# team_throttle_control_draft_2.net
KiCad netlist of a schematic drawn in EAGLE
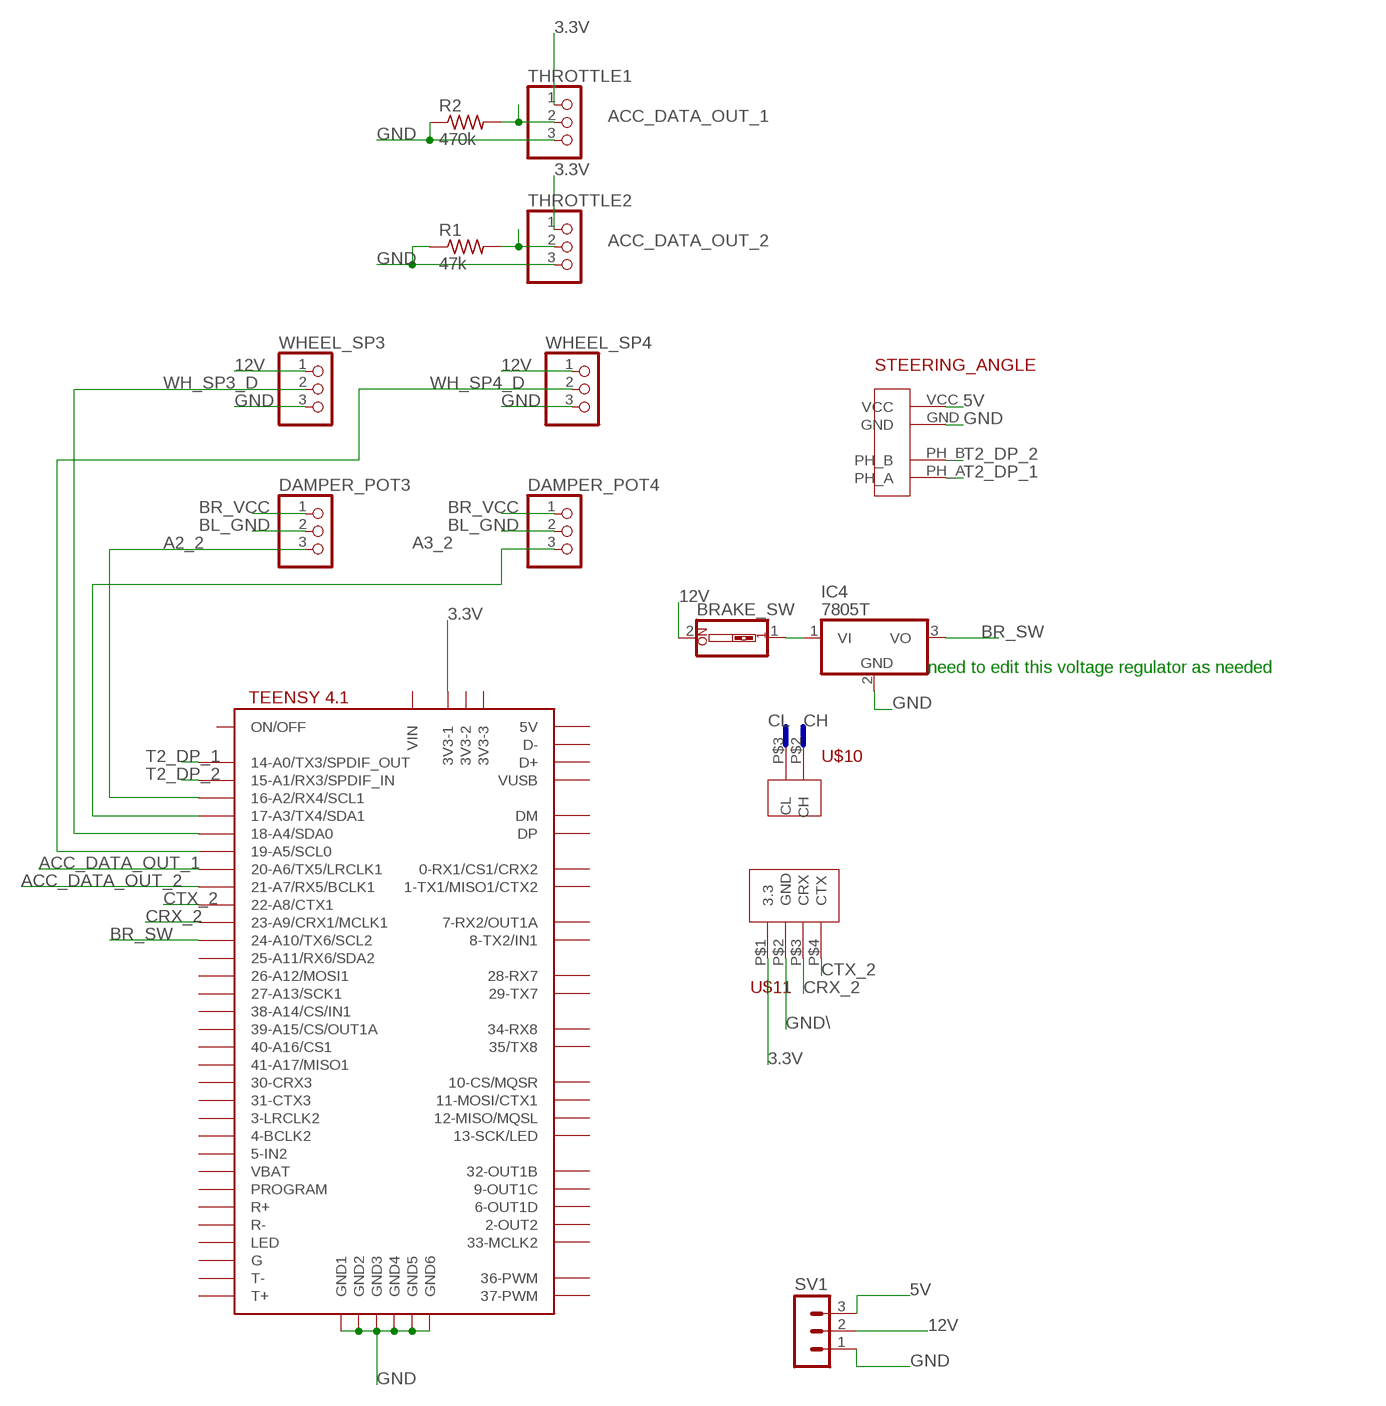
[diagram p0: schematic, sheet 1]

(export (version "E")
  (design (tool "Eeschema 10.0.6"))
  (components
    (comp (ref "BRAKE_SW")
      (value "SW_DIP-1")
      (footprint "eagle-import:EDG-01")
      (libsource (lib "eagle-import") (part "SW_DIP-1"))
    )
    (comp (ref "DAMPER_POT3")
      (value "PINHD-1X3CB")
      (footprint "eagle-import:1X03-CLEANBIG")
      (libsource (lib "eagle-import") (part "PINHD-1X3CB"))
    )
    (comp (ref "DAMPER_POT4")
      (value "PINHD-1X3CB")
      (footprint "eagle-import:1X03-CLEANBIG")
      (libsource (lib "eagle-import") (part "PINHD-1X3CB"))
    )
    (comp (ref "IC4")
      (value "7805T")
      (footprint "eagle-import:TO220H")
      (libsource (lib "eagle-import") (part "78T05"))
    )
    (comp (ref "R1")
      (value "47k")
      (footprint "eagle-import:0204_7")
      (libsource (lib "eagle-import") (part "R-US_0204/7"))
    )
    (comp (ref "R2")
      (value "470k")
      (footprint "eagle-import:0204_7")
      (libsource (lib "eagle-import") (part "R-US_0204/7"))
    )
    (comp (ref "STEERING_ANGLE")
      (value "ROTARY_ENCODER")
      (footprint "eagle-import:ROTARY_ENCODER")
      (libsource (lib "eagle-import") (part "ROTARY_ENCODER"))
    )
    (comp (ref "SV1")
      (value "MA03-1")
      (footprint "eagle-import:MA03-1")
      (libsource (lib "eagle-import") (part "MA03-1"))
    )
    (comp (ref "THROTTLE1")
      (value "PINHD-1X3")
      (footprint "eagle-import:1X03")
      (libsource (lib "eagle-import") (part "PINHD-1X3"))
    )
    (comp (ref "THROTTLE2")
      (value "PINHD-1X3")
      (footprint "eagle-import:1X03")
      (libsource (lib "eagle-import") (part "PINHD-1X3"))
    )
    (comp (ref "U$3")
      (value "TEENSY41")
      (footprint "eagle-import:TEENSY41")
      (libsource (lib "eagle-import") (part "TEENSY41"))
    )
    (comp (ref "U$10")
      (value "CAN_BUS")
      (footprint "eagle-import:CAN_BUS")
      (libsource (lib "eagle-import") (part "CAN_BUS"))
    )
    (comp (ref "U$11")
      (value "CAN_TEE")
      (footprint "eagle-import:CAN_TEN")
      (libsource (lib "eagle-import") (part "CAN_TEE"))
    )
    (comp (ref "WHEEL_SP3")
      (value "PINHD-1X3")
      (footprint "eagle-import:1X03")
      (libsource (lib "eagle-import") (part "PINHD-1X3"))
    )
    (comp (ref "WHEEL_SP4")
      (value "PINHD-1X3")
      (footprint "eagle-import:1X03")
      (libsource (lib "eagle-import") (part "PINHD-1X3"))
    )
  )
  (nets
    (net (code "3") (name "/3.3V") (class "Default")
      (node (ref "THROTTLE1") (pin "1") (pinfunction "1_1") (pintype "passive"))
      (node (ref "THROTTLE2") (pin "1") (pinfunction "1_1") (pintype "passive"))
      (node (ref "U$11") (pin "P$1") (pinfunction "3.3_P$1") (pintype "bidirectional"))
      (node (ref "U$3") (pin "3V3-1") (pinfunction "3V3-1_3V3-1") (pintype "bidirectional"))
    )
    (net (code "4") (name "/5V") (class "Default")
      (node (ref "STEERING_ANGLE") (pin "VCC") (pinfunction "VCC_VCC") (pintype "bidirectional"))
      (node (ref "SV1") (pin "3") (pinfunction "3_3") (pintype "passive"))
    )
    (net (code "5") (name "/12V") (class "Default")
      (node (ref "BRAKE_SW") (pin "2") (pinfunction "2_2") (pintype "passive"))
      (node (ref "SV1") (pin "2") (pinfunction "2_2") (pintype "passive"))
      (node (ref "WHEEL_SP3") (pin "1") (pinfunction "1_1") (pintype "passive"))
      (node (ref "WHEEL_SP4") (pin "1") (pinfunction "1_1") (pintype "passive"))
    )
    (net (code "6") (name "/A2_2") (class "Default")
      (node (ref "DAMPER_POT3") (pin "3") (pinfunction "3_3") (pintype "passive"))
      (node (ref "U$3") (pin "16-A2/RX4/SCL1") (pinfunction "16-A2/RX4/SCL1_16-A2/RX4/SCL1") (pintype "bidirectional"))
    )
    (net (code "7") (name "/A3_2") (class "Default")
      (node (ref "DAMPER_POT4") (pin "3") (pinfunction "3_3") (pintype "passive"))
      (node (ref "U$3") (pin "17-A3/TX4/SDA1") (pinfunction "17-A3/TX4/SDA1_17-A3/TX4/SDA1") (pintype "bidirectional"))
    )
    (net (code "8") (name "/ACC_DATA_OUT_1") (class "Default")
      (node (ref "R2") (pin "2") (pinfunction "2_2") (pintype "passive"))
      (node (ref "THROTTLE1") (pin "2") (pinfunction "2_2") (pintype "passive"))
      (node (ref "U$3") (pin "20-A6/TX5/LRCLK1") (pinfunction "20-A6/TX5/LRCLK1_20-A6/TX5/LRCLK1") (pintype "bidirectional"))
    )
    (net (code "9") (name "/ACC_DATA_OUT_2") (class "Default")
      (node (ref "R1") (pin "2") (pinfunction "2_2") (pintype "passive"))
      (node (ref "THROTTLE2") (pin "2") (pinfunction "2_2") (pintype "passive"))
      (node (ref "U$3") (pin "21-A7/RX5/BCLK1") (pinfunction "21-A7/RX5/BCLK1_21-A7/RX5/BCLK1") (pintype "bidirectional"))
    )
    (net (code "10") (name "/BL_GND") (class "Default")
      (node (ref "DAMPER_POT3") (pin "2") (pinfunction "2_2") (pintype "passive"))
      (node (ref "DAMPER_POT4") (pin "2") (pinfunction "2_2") (pintype "passive"))
    )
    (net (code "11") (name "/BR_SW") (class "Default")
      (node (ref "IC4") (pin "3") (pinfunction "VO_3") (pintype "passive"))
      (node (ref "U$3") (pin "24-A10/TX6/SCL2") (pinfunction "24-A10/TX6/SCL2_24-A10/TX6/SCL2") (pintype "bidirectional"))
    )
    (net (code "12") (name "/BR_VCC") (class "Default")
      (node (ref "DAMPER_POT3") (pin "1") (pinfunction "1_1") (pintype "passive"))
      (node (ref "DAMPER_POT4") (pin "1") (pinfunction "1_1") (pintype "passive"))
    )
    (net (code "13") (name "/CRX_2") (class "Default")
      (node (ref "U$11") (pin "P$3") (pinfunction "CRX_P$3") (pintype "bidirectional"))
      (node (ref "U$3") (pin "23-A9/CRX1/MCLK1") (pinfunction "23-A9/CRX1/MCLK1_23-A9/CRX1/MCLK1") (pintype "bidirectional"))
    )
    (net (code "14") (name "/CTX_2") (class "Default")
      (node (ref "U$11") (pin "P$4") (pinfunction "CTX_P$4") (pintype "bidirectional"))
      (node (ref "U$3") (pin "22-A8/CTX1") (pinfunction "22-A8/CTX1_22-A8/CTX1") (pintype "bidirectional"))
    )
    (net (code "15") (name "/GND") (class "Default")
      (node (ref "IC4") (pin "2") (pinfunction "GND_2") (pintype "passive"))
      (node (ref "R1") (pin "1") (pinfunction "1_1") (pintype "passive"))
      (node (ref "R2") (pin "1") (pinfunction "1_1") (pintype "passive"))
      (node (ref "STEERING_ANGLE") (pin "GND") (pinfunction "GND_GND") (pintype "bidirectional"))
      (node (ref "SV1") (pin "1") (pinfunction "1_1") (pintype "passive"))
      (node (ref "THROTTLE1") (pin "3") (pinfunction "3_3") (pintype "passive"))
      (node (ref "THROTTLE2") (pin "3") (pinfunction "3_3") (pintype "passive"))
      (node (ref "U$3") (pin "GND1") (pinfunction "GND1_GND1") (pintype "bidirectional"))
      (node (ref "U$3") (pin "GND2") (pinfunction "GND2_GND2") (pintype "bidirectional"))
      (node (ref "U$3") (pin "GND3") (pinfunction "GND3_GND3") (pintype "bidirectional"))
      (node (ref "U$3") (pin "GND4") (pinfunction "GND4_GND4") (pintype "bidirectional"))
      (node (ref "U$3") (pin "GND5") (pinfunction "GND5_GND5") (pintype "bidirectional"))
      (node (ref "U$3") (pin "GND6") (pinfunction "GND6_GND6") (pintype "bidirectional"))
      (node (ref "WHEEL_SP3") (pin "3") (pinfunction "3_3") (pintype "passive"))
      (node (ref "WHEEL_SP4") (pin "3") (pinfunction "3_3") (pintype "passive"))
    )
    (net (code "16") (name "/GND\\") (class "Default")
      (node (ref "U$11") (pin "P$2") (pinfunction "GND_P$2") (pintype "bidirectional"))
    )
    (net (code "17") (name "/T2_DP_1") (class "Default")
      (node (ref "STEERING_ANGLE") (pin "PH_A") (pinfunction "PH_A_PH_A") (pintype "bidirectional"))
      (node (ref "U$3") (pin "14-A0/TX3/SPDIF_OUT") (pinfunction "14-A0/TX3/SPDIF_OUT_14-A0/TX3/SPDIF_OUT") (pintype "bidirectional"))
    )
    (net (code "18") (name "/T2_DP_2") (class "Default")
      (node (ref "STEERING_ANGLE") (pin "PH_B") (pinfunction "PH_B_PH_B") (pintype "bidirectional"))
      (node (ref "U$3") (pin "15-A1/RX3/SPDIF_IN") (pinfunction "15-A1/RX3/SPDIF_IN_15-A1/RX3/SPDIF_IN") (pintype "bidirectional"))
    )
    (net (code "19") (name "/WH_SP3_D") (class "Default")
      (node (ref "U$3") (pin "18-A4/SDA0") (pinfunction "18-A4/SDA0_18-A4/SDA0") (pintype "bidirectional"))
      (node (ref "WHEEL_SP3") (pin "2") (pinfunction "2_2") (pintype "passive"))
    )
    (net (code "20") (name "/WH_SP4_D") (class "Default")
      (node (ref "U$3") (pin "19-A5/SCL0") (pinfunction "19-A5/SCL0_19-A5/SCL0") (pintype "bidirectional"))
      (node (ref "WHEEL_SP4") (pin "2") (pinfunction "2_2") (pintype "passive"))
    )
    (net (code "21") (name "/{CH}") (class "Default")
      (node (ref "U$10") (pin "P$2") (pinfunction "CH_P$2") (pintype "bidirectional"))
    )
    (net (code "22") (name "/{CL}") (class "Default")
      (node (ref "U$10") (pin "P$3") (pinfunction "CL_P$3") (pintype "bidirectional"))
    )
    (net (code "23") (name "Net-(IC4-VI)") (class "Default")
      (node (ref "BRAKE_SW") (pin "1") (pinfunction "1_1") (pintype "passive"))
      (node (ref "IC4") (pin "1") (pinfunction "VI_1") (pintype "input"))
    )
    (net (code "24") (name "unconnected-(U$3-5V-Pad+5V)") (class "Default")
      (node (ref "U$3") (pin "+5V") (pinfunction "5V_+5V") (pintype "bidirectional"))
    )
    (net (code "25") (name "unconnected-(U$3-8-TX2{slash}IN1-Pad8-TX2{slash}IN2)") (class "Default")
      (node (ref "U$3") (pin "8-TX2/IN2") (pinfunction "8-TX2/IN1_8-TX2/IN2") (pintype "bidirectional"))
    )
    (net (code "26") (name "unconnected-(U$3-10-CS{slash}MQSR-Pad10-CS\\MQSR)") (class "Default")
      (node (ref "U$3") (pin "10-CS\\MQSR") (pinfunction "10-CS/MQSR_10-CS\\MQSR") (pintype "bidirectional"))
    )
    (net (code "27") (name "unconnected-(U$3-35{slash}TX8-Pad35-TX8)") (class "Default")
      (node (ref "U$3") (pin "35-TX8") (pinfunction "35/TX8_35-TX8") (pintype "bidirectional"))
    )
    (net (code "28") (name "unconnected-(U$3-Pad0-RX1{slash}CS1{slash}CRX2)") (class "Default")
      (node (ref "U$3") (pin "0-RX1/CS1/CRX2") (pinfunction "0-RX1/CS1/CRX2_0-RX1/CS1/CRX2") (pintype "bidirectional"))
    )
    (net (code "29") (name "unconnected-(U$3-Pad1-TX1{slash}MISO1{slash}CTX2)") (class "Default")
      (node (ref "U$3") (pin "1-TX1/MISO1/CTX2") (pinfunction "1-TX1/MISO1/CTX2_1-TX1/MISO1/CTX2") (pintype "bidirectional"))
    )
    (net (code "30") (name "unconnected-(U$3-Pad2-OUT2)") (class "Default")
      (node (ref "U$3") (pin "2-OUT2") (pinfunction "2-OUT2_2-OUT2") (pintype "bidirectional"))
    )
    (net (code "31") (name "unconnected-(U$3-Pad3-LRCLK2)") (class "Default")
      (node (ref "U$3") (pin "3-LRCLK2") (pinfunction "3-LRCLK2_3-LRCLK2") (pintype "bidirectional"))
    )
    (net (code "32") (name "unconnected-(U$3-Pad3V3-2)") (class "Default")
      (node (ref "U$3") (pin "3V3-2") (pinfunction "3V3-2_3V3-2") (pintype "bidirectional"))
    )
    (net (code "33") (name "unconnected-(U$3-Pad3V3-3)") (class "Default")
      (node (ref "U$3") (pin "3V3-3") (pinfunction "3V3-3_3V3-3") (pintype "bidirectional"))
    )
    (net (code "34") (name "unconnected-(U$3-Pad4-BCLK2)") (class "Default")
      (node (ref "U$3") (pin "4-BCLK2") (pinfunction "4-BCLK2_4-BCLK2") (pintype "bidirectional"))
    )
    (net (code "35") (name "unconnected-(U$3-Pad5-IN2)") (class "Default")
      (node (ref "U$3") (pin "5-IN2") (pinfunction "5-IN2_5-IN2") (pintype "bidirectional"))
    )
    (net (code "36") (name "unconnected-(U$3-Pad6-OUT1D)") (class "Default")
      (node (ref "U$3") (pin "6-OUT1D") (pinfunction "6-OUT1D_6-OUT1D") (pintype "bidirectional"))
    )
    (net (code "37") (name "unconnected-(U$3-Pad7-RX2{slash}OUT1A)") (class "Default")
      (node (ref "U$3") (pin "7-RX2/OUT1A") (pinfunction "7-RX2/OUT1A_7-RX2/OUT1A") (pintype "bidirectional"))
    )
    (net (code "38") (name "unconnected-(U$3-Pad9-OUT1C)") (class "Default")
      (node (ref "U$3") (pin "9-OUT1C") (pinfunction "9-OUT1C_9-OUT1C") (pintype "bidirectional"))
    )
    (net (code "39") (name "unconnected-(U$3-Pad11-MOSI{slash}CTX1)") (class "Default")
      (node (ref "U$3") (pin "11-MOSI/CTX1") (pinfunction "11-MOSI/CTX1_11-MOSI/CTX1") (pintype "bidirectional"))
    )
    (net (code "40") (name "unconnected-(U$3-Pad12-MISO{slash}MQSL)") (class "Default")
      (node (ref "U$3") (pin "12-MISO/MQSL") (pinfunction "12-MISO/MQSL_12-MISO/MQSL") (pintype "bidirectional"))
    )
    (net (code "41") (name "unconnected-(U$3-Pad13-SCK{slash}LED)") (class "Default")
      (node (ref "U$3") (pin "13-SCK/LED") (pinfunction "13-SCK/LED_13-SCK/LED") (pintype "bidirectional"))
    )
    (net (code "42") (name "unconnected-(U$3-Pad25-A11{slash}RX6{slash}SDA2)") (class "Default")
      (node (ref "U$3") (pin "25-A11/RX6/SDA2") (pinfunction "25-A11/RX6/SDA2_25-A11/RX6/SDA2") (pintype "bidirectional"))
    )
    (net (code "43") (name "unconnected-(U$3-Pad26-A12{slash}MOSI1)") (class "Default")
      (node (ref "U$3") (pin "26-A12/MOSI1") (pinfunction "26-A12/MOSI1_26-A12/MOSI1") (pintype "bidirectional"))
    )
    (net (code "44") (name "unconnected-(U$3-Pad27-A13{slash}SCK1)") (class "Default")
      (node (ref "U$3") (pin "27-A13/SCK1") (pinfunction "27-A13/SCK1_27-A13/SCK1") (pintype "bidirectional"))
    )
    (net (code "45") (name "unconnected-(U$3-Pad28-RX7)") (class "Default")
      (node (ref "U$3") (pin "28-RX7") (pinfunction "28-RX7_28-RX7") (pintype "bidirectional"))
    )
    (net (code "46") (name "unconnected-(U$3-Pad29-TX7)") (class "Default")
      (node (ref "U$3") (pin "29-TX7") (pinfunction "29-TX7_29-TX7") (pintype "bidirectional"))
    )
    (net (code "47") (name "unconnected-(U$3-Pad30-CRX3)") (class "Default")
      (node (ref "U$3") (pin "30-CRX3") (pinfunction "30-CRX3_30-CRX3") (pintype "bidirectional"))
    )
    (net (code "48") (name "unconnected-(U$3-Pad31-CTX3)") (class "Default")
      (node (ref "U$3") (pin "31-CTX3") (pinfunction "31-CTX3_31-CTX3") (pintype "bidirectional"))
    )
    (net (code "49") (name "unconnected-(U$3-Pad32-OUT1B)") (class "Default")
      (node (ref "U$3") (pin "32-OUT1B") (pinfunction "32-OUT1B_32-OUT1B") (pintype "bidirectional"))
    )
    (net (code "50") (name "unconnected-(U$3-Pad33-MCLK2)") (class "Default")
      (node (ref "U$3") (pin "33-MCLK2") (pinfunction "33-MCLK2_33-MCLK2") (pintype "bidirectional"))
    )
    (net (code "51") (name "unconnected-(U$3-Pad34-RX8)") (class "Default")
      (node (ref "U$3") (pin "34-RX8") (pinfunction "34-RX8_34-RX8") (pintype "bidirectional"))
    )
    (net (code "52") (name "unconnected-(U$3-Pad36-PWM)") (class "Default")
      (node (ref "U$3") (pin "36-PWM") (pinfunction "36-PWM_36-PWM") (pintype "bidirectional"))
    )
    (net (code "53") (name "unconnected-(U$3-Pad37-PWM)") (class "Default")
      (node (ref "U$3") (pin "37-PWM") (pinfunction "37-PWM_37-PWM") (pintype "bidirectional"))
    )
    (net (code "54") (name "unconnected-(U$3-Pad38-A14{slash}CS{slash}IN1)") (class "Default")
      (node (ref "U$3") (pin "38-A14/CS/IN1") (pinfunction "38-A14/CS/IN1_38-A14/CS/IN1") (pintype "bidirectional"))
    )
    (net (code "55") (name "unconnected-(U$3-Pad39-A15{slash}CS{slash}OUT1A)") (class "Default")
      (node (ref "U$3") (pin "39-A15/CS/OUT1A") (pinfunction "39-A15/CS/OUT1A_39-A15/CS/OUT1A") (pintype "bidirectional"))
    )
    (net (code "56") (name "unconnected-(U$3-Pad40-A16{slash}CS1)") (class "Default")
      (node (ref "U$3") (pin "40-A16/CS1") (pinfunction "40-A16/CS1_40-A16/CS1") (pintype "bidirectional"))
    )
    (net (code "57") (name "unconnected-(U$3-Pad41-A17{slash}MISO1)") (class "Default")
      (node (ref "U$3") (pin "41-A17/MISO1") (pinfunction "41-A17/MISO1_41-A17/MISO1") (pintype "bidirectional"))
    )
    (net (code "58") (name "unconnected-(U$3-PadD+)") (class "Default")
      (node (ref "U$3") (pin "D+") (pinfunction "D+_D+") (pintype "bidirectional"))
    )
    (net (code "59") (name "unconnected-(U$3-PadD-)") (class "Default")
      (node (ref "U$3") (pin "D-") (pinfunction "D-_D-") (pintype "bidirectional"))
    )
    (net (code "60") (name "unconnected-(U$3-PadDM)") (class "Default")
      (node (ref "U$3") (pin "DM") (pinfunction "DM_DM") (pintype "bidirectional"))
    )
    (net (code "61") (name "unconnected-(U$3-PadDP)") (class "Default")
      (node (ref "U$3") (pin "DP") (pinfunction "DP_DP") (pintype "bidirectional"))
    )
    (net (code "62") (name "unconnected-(U$3-PadG)") (class "Default")
      (node (ref "U$3") (pin "G") (pinfunction "G_G") (pintype "bidirectional"))
    )
    (net (code "63") (name "unconnected-(U$3-PadLED)") (class "Default")
      (node (ref "U$3") (pin "LED") (pinfunction "LED_LED") (pintype "bidirectional"))
    )
    (net (code "64") (name "unconnected-(U$3-PadON{slash}OFF)") (class "Default")
      (node (ref "U$3") (pin "ON/OFF") (pinfunction "ON/OFF_ON/OFF") (pintype "bidirectional"))
    )
    (net (code "65") (name "unconnected-(U$3-PadPROGRAM)") (class "Default")
      (node (ref "U$3") (pin "PROGRAM") (pinfunction "PROGRAM_PROGRAM") (pintype "bidirectional"))
    )
    (net (code "66") (name "unconnected-(U$3-PadR+)") (class "Default")
      (node (ref "U$3") (pin "R+") (pinfunction "R+_R+") (pintype "bidirectional"))
    )
    (net (code "67") (name "unconnected-(U$3-PadR-)") (class "Default")
      (node (ref "U$3") (pin "R-") (pinfunction "R-_R-") (pintype "bidirectional"))
    )
    (net (code "68") (name "unconnected-(U$3-PadT+)") (class "Default")
      (node (ref "U$3") (pin "T+") (pinfunction "T+_T+") (pintype "bidirectional"))
    )
    (net (code "69") (name "unconnected-(U$3-PadT-)") (class "Default")
      (node (ref "U$3") (pin "T-") (pinfunction "T-_T-") (pintype "bidirectional"))
    )
    (net (code "70") (name "unconnected-(U$3-PadVBAT)") (class "Default")
      (node (ref "U$3") (pin "VBAT") (pinfunction "VBAT_VBAT") (pintype "bidirectional"))
    )
    (net (code "71") (name "unconnected-(U$3-PadVIN)") (class "Default")
      (node (ref "U$3") (pin "VIN") (pinfunction "VIN_VIN") (pintype "bidirectional"))
    )
    (net (code "72") (name "unconnected-(U$3-PadVUSB)") (class "Default")
      (node (ref "U$3") (pin "VUSB") (pinfunction "VUSB_VUSB") (pintype "bidirectional"))
    )
  )
)
